# XM-10_Typical_Application_Circuit.net
KiCad netlist of a schematic drawn in Altium Designer
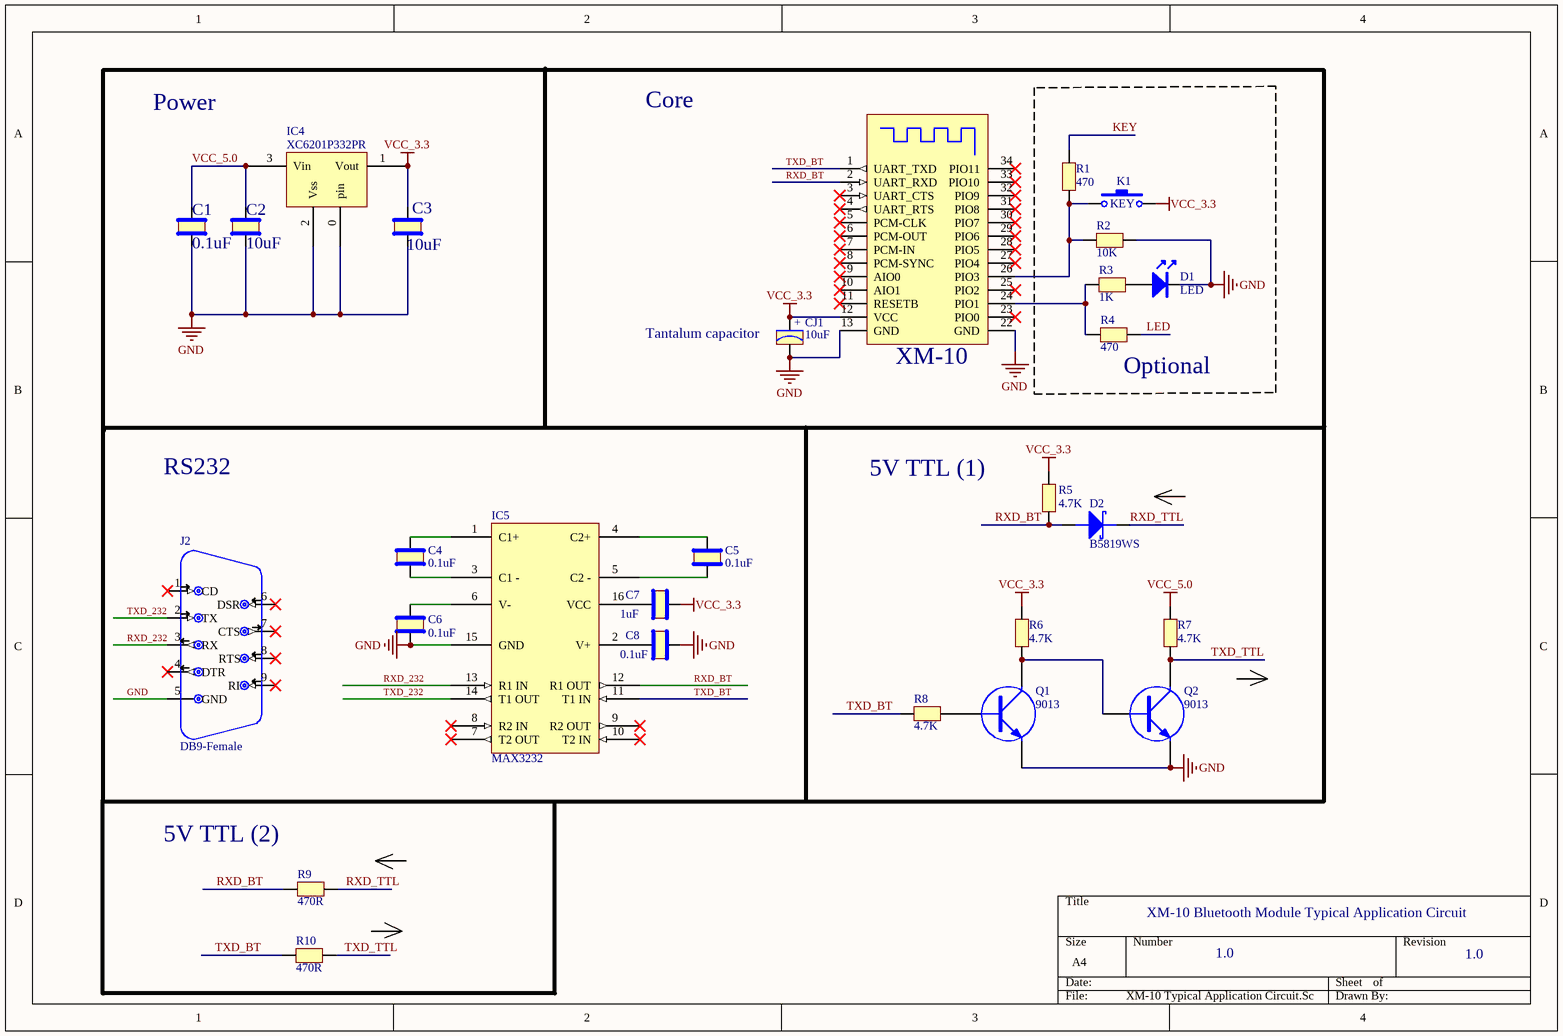
[diagram p0: XM-10 Typical Application Circuit.SchDoc]

(export (version "E")
  (design (tool "Eeschema 10.0.6"))
  (components
    (comp (ref "*1") (value "XM-10") (libsource (lib "wbh") (part "XM-101")))
    (comp (ref "C1") (value "0.1uF") (footprint "0603.RC") (libsource (lib "*") (part "CAP")))
    (comp (ref "C2") (value "10uF") (footprint "0603.RC") (libsource (lib "*") (part "CAP")))
    (comp (ref "C3") (value "10uF") (footprint "0603.RC") (libsource (lib "*") (part "CAP")))
    (comp (ref "C4") (value "0.1uF") (footprint "0603.RC") (libsource (lib "*") (part "CAP")))
    (comp (ref "C5") (value "0.1uF") (footprint "0603.RC") (libsource (lib "") (part "CAP_2")))
    (comp (ref "C6") (value "0.1uF") (footprint "0603.RC") (libsource (lib "*") (part "CAP")))
    (comp (ref "C7") (value "1uF") (footprint "0603.RC") (libsource (lib "") (part "CAP_1")))
    (comp (ref "C8") (value "0.1uF") (footprint "0603.RC") (libsource (lib "") (part "CAP_1")))
    (comp (ref "CJ1") (value "10uF") (footprint "1206.DC") (libsource (lib "wbh") (part "CAPJS")))
    (comp (ref "D1") (value "LED") (footprint "0603+") (libsource (lib "*") (part "LED")))
    (comp (ref "D2")
      (value "B5819WS")
      (footprint "SOD-323 - SMT")
      (description "Schottky Diode")
      (libsource (lib "wbh") (part "DIODE SCHOTTKY"))
    )
    (comp (ref "IC4") (value "XC6201P332PR") (footprint "SOT-89") (libsource (lib "*") (part "XC6201P301PR")))
    (comp (ref "IC5") (value "MAX3232") (footprint "SOP-16(N)") (libsource (lib "wbh") (part "MAX3232")))
    (comp (ref "J2") (value "DB9-Female") (footprint "DB9-F - 90") (libsource (lib "wbh") (part "DB9-F")))
    (comp (ref "K1") (value "KEY") (footprint "KEY-SS204") (libsource (lib "wbh") (part "SW-KEYSMT1")))
    (comp (ref "Q1")
      (value "9013")
      (footprint "SMT-SOT23MOS")
      (description "NPN Transistor")
      (libsource (lib "wbh") (part "NPN"))
    )
    (comp (ref "Q2")
      (value "9013")
      (footprint "SMT-SOT23MOS")
      (description "NPN Transistor")
      (libsource (lib "wbh") (part "NPN"))
    )
    (comp (ref "R1") (value "470") (footprint "0603.RC") (libsource (lib "") (part "RES_1")))
    (comp (ref "R2") (value "10K") (footprint "0603.RC") (libsource (lib "") (part "RES_3")))
    (comp (ref "R3") (value "1K") (footprint "0603.RC") (libsource (lib "") (part "RES_3")))
    (comp (ref "R4") (value "470") (footprint "0603.RC") (libsource (lib "") (part "RES_3")))
    (comp (ref "R5") (value "4.7K") (footprint "0603.RC") (libsource (lib "") (part "RES_2")))
    (comp (ref "R6") (value "4.7K") (footprint "0603.RC") (libsource (lib "wbh") (part "RES")))
    (comp (ref "R7") (value "4.7K") (footprint "0603.RC") (libsource (lib "wbh") (part "RES")))
    (comp (ref "R8") (value "4.7K") (footprint "0603.RC") (libsource (lib "") (part "RES_1")))
    (comp (ref "R9") (value "470R") (footprint "0603.RC") (libsource (lib "") (part "RES_1")))
    (comp (ref "R10") (value "470R") (footprint "0603.RC") (libsource (lib "") (part "RES_1")))
  )
  (nets
    (net (code "1") (name "/KEY") (class "Default")
      (node (ref "R1") (pin "1") (pinfunction "1_1") (pintype "passive"))
    )
    (net (code "2") (name "/LED") (class "Default")
      (node (ref "R4") (pin "1") (pinfunction "1_1") (pintype "passive"))
    )
    (net (code "3") (name "/RXD_232") (class "Default")
      (node (ref "IC5") (pin "13") (pinfunction "R1_IN_13") (pintype "input"))
      (node (ref "J2") (pin "3") (pinfunction "RX_3") (pintype "output"))
    )
    (net (code "4") (name "/RXD_BT") (class "Default")
      (node (ref "*1") (pin "2") (pinfunction "UART_RXD_2") (pintype "input"))
      (node (ref "D2") (pin "1") (pinfunction "1_1") (pintype "passive"))
      (node (ref "IC5") (pin "12") (pinfunction "R1_OUT_12") (pintype "output"))
      (node (ref "R5") (pin "1") (pinfunction "1_1") (pintype "passive"))
      (node (ref "R9") (pin "2") (pinfunction "2_2") (pintype "passive"))
    )
    (net (code "5") (name "/RXD_TTL") (class "Default")
      (node (ref "D2") (pin "2") (pinfunction "2_2") (pintype "passive"))
      (node (ref "R9") (pin "1") (pinfunction "1_1") (pintype "passive"))
    )
    (net (code "6") (name "/TXD_232") (class "Default")
      (node (ref "IC5") (pin "14") (pinfunction "T1_OUT_14") (pintype "output"))
      (node (ref "J2") (pin "2") (pinfunction "TX_2") (pintype "input"))
    )
    (net (code "7") (name "/TXD_BT") (class "Default")
      (node (ref "*1") (pin "1") (pinfunction "UART_TXD_1") (pintype "output"))
      (node (ref "IC5") (pin "11") (pinfunction "T1_IN_11") (pintype "input"))
      (node (ref "R10") (pin "2") (pinfunction "2_2") (pintype "passive"))
      (node (ref "R8") (pin "2") (pinfunction "2_2") (pintype "passive"))
    )
    (net (code "8") (name "/TXD_TTL") (class "Default")
      (node (ref "Q2") (pin "D") (pinfunction "D_D") (pintype "passive"))
      (node (ref "R10") (pin "1") (pinfunction "1_1") (pintype "passive"))
      (node (ref "R7") (pin "1") (pinfunction "1_1") (pintype "passive"))
    )
    (net (code "9") (name "GND") (class "Default")
      (node (ref "*1") (pin "13") (pinfunction "GND_13") (pintype "passive"))
      (node (ref "*1") (pin "22") (pinfunction "GND_22") (pintype "passive"))
      (node (ref "C1") (pin "1") (pinfunction "1_1") (pintype "passive"))
      (node (ref "C2") (pin "1") (pinfunction "1_1") (pintype "passive"))
      (node (ref "C3") (pin "1") (pinfunction "1_1") (pintype "passive"))
      (node (ref "C6") (pin "1") (pinfunction "1_1") (pintype "passive"))
      (node (ref "C8") (pin "1") (pinfunction "1_1") (pintype "passive"))
      (node (ref "CJ1") (pin "K") (pinfunction "K_K") (pintype "passive"))
      (node (ref "D1") (pin "K") (pintype "passive"))
      (node (ref "IC4") (pin "0") (pinfunction "pin_0") (pintype "passive"))
      (node (ref "IC4") (pin "2") (pinfunction "Vss_2") (pintype "passive"))
      (node (ref "IC5") (pin "15") (pinfunction "GND_15") (pintype "power_in"))
      (node (ref "J2") (pin "5") (pinfunction "GND_5") (pintype "power_in"))
      (node (ref "Q1") (pin "S") (pinfunction "S_S") (pintype "passive"))
      (node (ref "Q2") (pin "S") (pinfunction "S_S") (pintype "passive"))
      (node (ref "R2") (pin "1") (pinfunction "1_1") (pintype "passive"))
    )
    (net (code "10") (name "Net-(*1-PIO1)") (class "Default")
      (node (ref "*1") (pin "24") (pinfunction "PIO1_24") (pintype "passive"))
      (node (ref "R3") (pin "2") (pinfunction "2_2") (pintype "passive"))
      (node (ref "R4") (pin "2") (pinfunction "2_2") (pintype "passive"))
    )
    (net (code "11") (name "Net-(*1-PIO3)") (class "Default")
      (node (ref "*1") (pin "26") (pinfunction "PIO3_26") (pintype "passive"))
      (node (ref "K1") (pin "2") (pinfunction "2_2") (pintype "passive"))
      (node (ref "R1") (pin "2") (pinfunction "2_2") (pintype "passive"))
      (node (ref "R2") (pin "2") (pinfunction "2_2") (pintype "passive"))
    )
    (net (code "12") (name "Net-(D1-PadA)") (class "Default")
      (node (ref "D1") (pin "A") (pintype "passive"))
      (node (ref "R3") (pin "1") (pinfunction "1_1") (pintype "passive"))
    )
    (net (code "13") (name "Net-(IC5-C1+)") (class "Default")
      (node (ref "C4") (pin "2") (pinfunction "2_2") (pintype "passive"))
      (node (ref "IC5") (pin "1") (pinfunction "C1+_1") (pintype "passive"))
    )
    (net (code "14") (name "Net-(IC5-C1_-)") (class "Default")
      (node (ref "C4") (pin "1") (pinfunction "1_1") (pintype "passive"))
      (node (ref "IC5") (pin "3") (pinfunction "C1_-_3") (pintype "passive"))
    )
    (net (code "15") (name "Net-(IC5-C2+)") (class "Default")
      (node (ref "C5") (pin "1") (pinfunction "1_1") (pintype "passive"))
      (node (ref "IC5") (pin "4") (pinfunction "C2+_4") (pintype "passive"))
    )
    (net (code "16") (name "Net-(IC5-C2_-)") (class "Default")
      (node (ref "C5") (pin "2") (pinfunction "2_2") (pintype "passive"))
      (node (ref "IC5") (pin "5") (pinfunction "C2_-_5") (pintype "passive"))
    )
    (net (code "17") (name "Net-(IC5-V+)") (class "Default")
      (node (ref "C8") (pin "2") (pinfunction "2_2") (pintype "passive"))
      (node (ref "IC5") (pin "2") (pinfunction "V+_2") (pintype "passive"))
    )
    (net (code "18") (name "Net-(IC5-V-)") (class "Default")
      (node (ref "C6") (pin "2") (pinfunction "2_2") (pintype "passive"))
      (node (ref "IC5") (pin "6") (pinfunction "V-_6") (pintype "power_in"))
    )
    (net (code "19") (name "Net-(IC5-VCC)") (class "Default")
      (node (ref "C7") (pin "2") (pinfunction "2_2") (pintype "passive"))
      (node (ref "IC5") (pin "16") (pinfunction "VCC_16") (pintype "power_in"))
    )
    (net (code "20") (name "Net-(Q1-PadD)") (class "Default")
      (node (ref "Q1") (pin "D") (pinfunction "D_D") (pintype "passive"))
      (node (ref "Q2") (pin "G") (pinfunction "G_G") (pintype "passive"))
      (node (ref "R6") (pin "1") (pinfunction "1_1") (pintype "passive"))
    )
    (net (code "21") (name "Net-(Q1-PadG)") (class "Default")
      (node (ref "Q1") (pin "G") (pinfunction "G_G") (pintype "passive"))
      (node (ref "R8") (pin "1") (pinfunction "1_1") (pintype "passive"))
    )
    (net (code "22") (name "VCC_3.3") (class "Default")
      (node (ref "*1") (pin "12") (pinfunction "VCC_12") (pintype "power_in"))
      (node (ref "C3") (pin "2") (pinfunction "2_2") (pintype "passive"))
      (node (ref "C7") (pin "1") (pinfunction "1_1") (pintype "passive"))
      (node (ref "CJ1") (pin "A") (pinfunction "A_A") (pintype "passive"))
      (node (ref "IC4") (pin "1") (pinfunction "Vout_1") (pintype "passive"))
      (node (ref "K1") (pin "1") (pinfunction "1_1") (pintype "passive"))
      (node (ref "R5") (pin "2") (pinfunction "2_2") (pintype "passive"))
      (node (ref "R6") (pin "2") (pinfunction "2_2") (pintype "passive"))
    )
    (net (code "23") (name "VCC_5.0") (class "Default")
      (node (ref "C1") (pin "2") (pinfunction "2_2") (pintype "passive"))
      (node (ref "C2") (pin "2") (pinfunction "2_2") (pintype "passive"))
      (node (ref "IC4") (pin "3") (pinfunction "Vin_3") (pintype "passive"))
      (node (ref "R7") (pin "2") (pinfunction "2_2") (pintype "passive"))
    )
    (net (code "24") (name "unconnected-(*1-AIO0-Pad9)") (class "Default")
      (node (ref "*1") (pin "9") (pinfunction "AIO0_9") (pintype "passive+no_connect"))
    )
    (net (code "25") (name "unconnected-(*1-AIO1-Pad10)") (class "Default")
      (node (ref "*1") (pin "10") (pinfunction "AIO1_10") (pintype "passive+no_connect"))
    )
    (net (code "26") (name "unconnected-(*1-PCM-CLK-Pad5)") (class "Default")
      (node (ref "*1") (pin "5") (pinfunction "PCM-CLK_5") (pintype "passive+no_connect"))
    )
    (net (code "27") (name "unconnected-(*1-PCM-IN-Pad7)") (class "Default")
      (node (ref "*1") (pin "7") (pinfunction "PCM-IN_7") (pintype "passive+no_connect"))
    )
    (net (code "28") (name "unconnected-(*1-PCM-OUT-Pad6)") (class "Default")
      (node (ref "*1") (pin "6") (pinfunction "PCM-OUT_6") (pintype "passive+no_connect"))
    )
    (net (code "29") (name "unconnected-(*1-PCM-SYNC-Pad8)") (class "Default")
      (node (ref "*1") (pin "8") (pinfunction "PCM-SYNC_8") (pintype "passive+no_connect"))
    )
    (net (code "30") (name "unconnected-(*1-PIO0-Pad23)") (class "Default")
      (node (ref "*1") (pin "23") (pinfunction "PIO0_23") (pintype "passive+no_connect"))
    )
    (net (code "31") (name "unconnected-(*1-PIO2-Pad25)") (class "Default")
      (node (ref "*1") (pin "25") (pinfunction "PIO2_25") (pintype "passive+no_connect"))
    )
    (net (code "32") (name "unconnected-(*1-PIO4-Pad27)") (class "Default")
      (node (ref "*1") (pin "27") (pinfunction "PIO4_27") (pintype "passive+no_connect"))
    )
    (net (code "33") (name "unconnected-(*1-PIO5-Pad28)") (class "Default")
      (node (ref "*1") (pin "28") (pinfunction "PIO5_28") (pintype "passive+no_connect"))
    )
    (net (code "34") (name "unconnected-(*1-PIO6-Pad29)") (class "Default")
      (node (ref "*1") (pin "29") (pinfunction "PIO6_29") (pintype "passive+no_connect"))
    )
    (net (code "35") (name "unconnected-(*1-PIO7-Pad30)") (class "Default")
      (node (ref "*1") (pin "30") (pinfunction "PIO7_30") (pintype "passive+no_connect"))
    )
    (net (code "36") (name "unconnected-(*1-PIO8-Pad31)") (class "Default")
      (node (ref "*1") (pin "31") (pinfunction "PIO8_31") (pintype "passive+no_connect"))
    )
    (net (code "37") (name "unconnected-(*1-PIO9-Pad32)") (class "Default")
      (node (ref "*1") (pin "32") (pinfunction "PIO9_32") (pintype "passive+no_connect"))
    )
    (net (code "38") (name "unconnected-(*1-PIO10-Pad33)") (class "Default")
      (node (ref "*1") (pin "33") (pinfunction "PIO10_33") (pintype "passive+no_connect"))
    )
    (net (code "39") (name "unconnected-(*1-PIO11-Pad34)") (class "Default")
      (node (ref "*1") (pin "34") (pinfunction "PIO11_34") (pintype "passive+no_connect"))
    )
    (net (code "40") (name "unconnected-(*1-RESETB-Pad11)") (class "Default")
      (node (ref "*1") (pin "11") (pinfunction "RESETB_11") (pintype "passive+no_connect"))
    )
    (net (code "41") (name "unconnected-(*1-UART_CTS-Pad3)") (class "Default")
      (node (ref "*1") (pin "3") (pinfunction "UART_CTS_3") (pintype "input+no_connect"))
    )
    (net (code "42") (name "unconnected-(*1-UART_RTS-Pad4)") (class "Default")
      (node (ref "*1") (pin "4") (pinfunction "UART_RTS_4") (pintype "output+no_connect"))
    )
    (net (code "43") (name "unconnected-(IC5-R2_IN-Pad8)") (class "Default")
      (node (ref "IC5") (pin "8") (pinfunction "R2_IN_8") (pintype "input+no_connect"))
    )
    (net (code "44") (name "unconnected-(IC5-R2_OUT-Pad9)") (class "Default")
      (node (ref "IC5") (pin "9") (pinfunction "R2_OUT_9") (pintype "output+no_connect"))
    )
    (net (code "45") (name "unconnected-(IC5-T2_IN-Pad10)") (class "Default")
      (node (ref "IC5") (pin "10") (pinfunction "T2_IN_10") (pintype "input+no_connect"))
    )
    (net (code "46") (name "unconnected-(IC5-T2_OUT-Pad7)") (class "Default")
      (node (ref "IC5") (pin "7") (pinfunction "T2_OUT_7") (pintype "output+no_connect"))
    )
    (net (code "47") (name "unconnected-(J2-CD-Pad1)") (class "Default")
      (node (ref "J2") (pin "1") (pinfunction "CD_1") (pintype "input+no_connect"))
    )
    (net (code "48") (name "unconnected-(J2-CTS-Pad7)") (class "Default")
      (node (ref "J2") (pin "7") (pinfunction "CTS_7") (pintype "output+no_connect"))
    )
    (net (code "49") (name "unconnected-(J2-DSR-Pad6)") (class "Default")
      (node (ref "J2") (pin "6") (pinfunction "DSR_6") (pintype "input+no_connect"))
    )
    (net (code "50") (name "unconnected-(J2-DTR-Pad4)") (class "Default")
      (node (ref "J2") (pin "4") (pinfunction "DTR_4") (pintype "output+no_connect"))
    )
    (net (code "51") (name "unconnected-(J2-RI-Pad9)") (class "Default")
      (node (ref "J2") (pin "9") (pinfunction "RI_9") (pintype "input+no_connect"))
    )
    (net (code "52") (name "unconnected-(J2-RTS-Pad8)") (class "Default")
      (node (ref "J2") (pin "8") (pinfunction "RTS_8") (pintype "input+no_connect"))
    )
  )
)
